# p2d-001.net
KiCad netlist of a schematic drawn in EAGLE
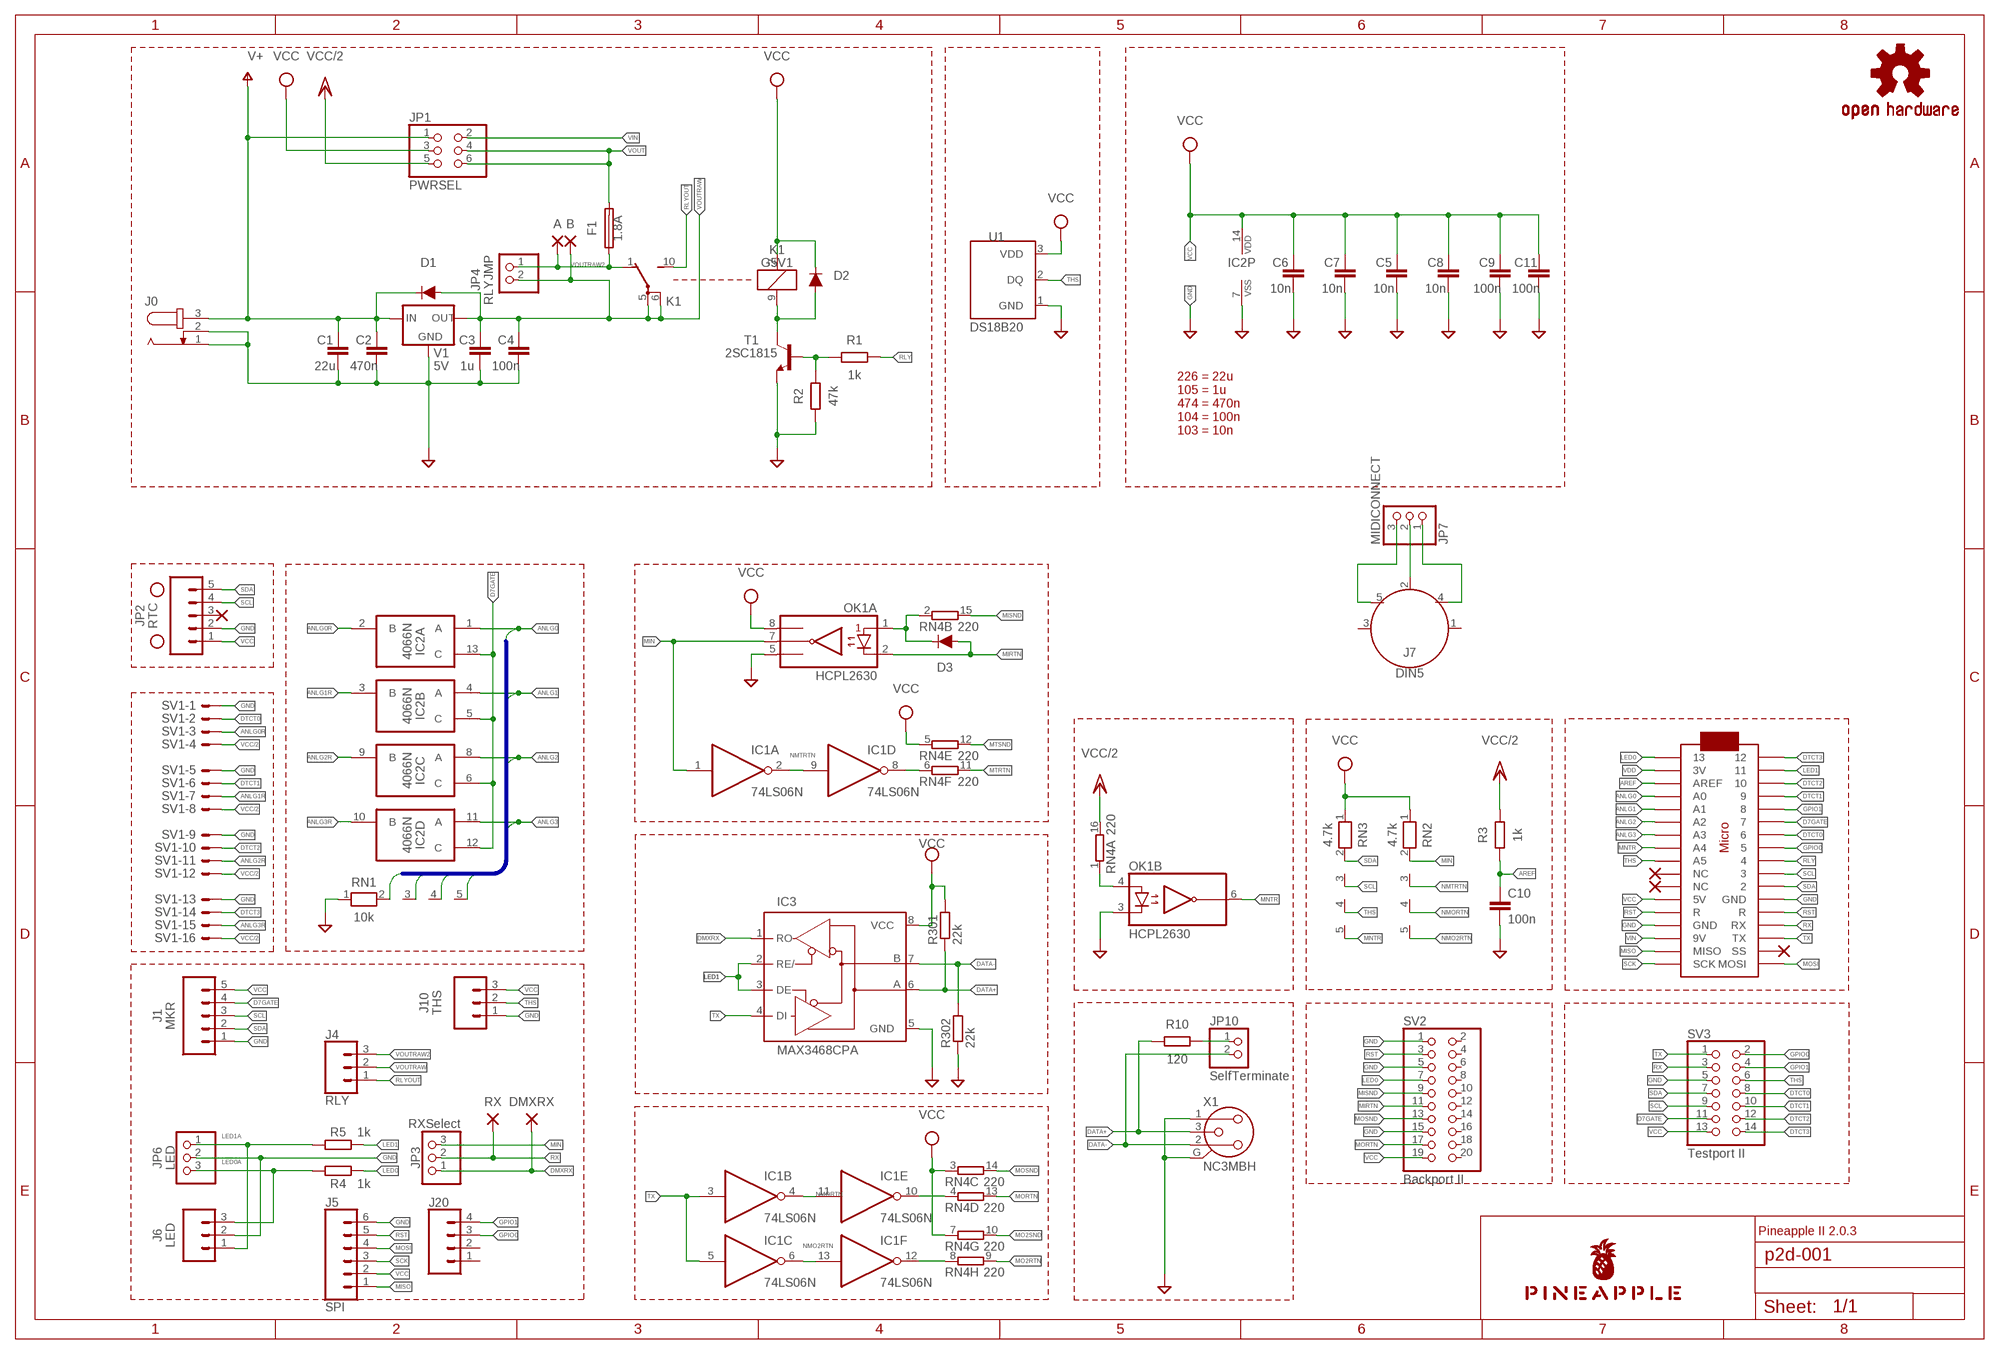
[diagram p0: schematic, sheet 1]

(export (version "E")
  (design (tool "Eeschema 10.0.6"))
  (components
    (comp (ref "A")
      (value "SMD2")
      (footprint "eagle-import:SMD1,27-2,54")
      (libsource (lib "eagle-import") (part "SMD2"))
    )
    (comp (ref "B")
      (value "SMD2")
      (footprint "eagle-import:SMD1,27-2,54")
      (libsource (lib "eagle-import") (part "SMD2"))
    )
    (comp (ref "C1")
      (value "22u")
      (footprint "eagle-import:C025-050X050")
      (libsource (lib "eagle-import") (part "C-EU025-050X050"))
    )
    (comp (ref "C2")
      (value "470n")
      (footprint "eagle-import:C050-024X044")
      (libsource (lib "eagle-import") (part "C-EU050-024X044"))
    )
    (comp (ref "C3")
      (value "1u")
      (footprint "eagle-import:C050-024X044")
      (libsource (lib "eagle-import") (part "C-EU050-024X044"))
    )
    (comp (ref "C4")
      (value "100n")
      (footprint "eagle-import:C025-024X044")
      (libsource (lib "eagle-import") (part "C-EU025-024X044"))
    )
    (comp (ref "C5")
      (value "10n")
      (footprint "eagle-import:C025-024X044")
      (libsource (lib "eagle-import") (part "resistor_348_C-EU025-024X044"))
    )
    (comp (ref "C6")
      (value "10n")
      (footprint "eagle-import:C025-024X044")
      (libsource (lib "eagle-import") (part "resistor_348_C-EU025-024X044"))
    )
    (comp (ref "C7")
      (value "10n")
      (footprint "eagle-import:C025-024X044")
      (libsource (lib "eagle-import") (part "resistor_348_C-EU025-024X044"))
    )
    (comp (ref "C8")
      (value "10n")
      (footprint "eagle-import:C025-024X044")
      (libsource (lib "eagle-import") (part "resistor_348_C-EU025-024X044"))
    )
    (comp (ref "C9")
      (value "100n")
      (footprint "eagle-import:C025-024X044")
      (libsource (lib "eagle-import") (part "resistor_348_C-EU025-024X044"))
    )
    (comp (ref "C10")
      (value "100n")
      (footprint "eagle-import:C025-024X044")
      (libsource (lib "eagle-import") (part "C-EU025-024X044"))
    )
    (comp (ref "C11")
      (value "100n")
      (footprint "eagle-import:C025-024X044")
      (libsource (lib "eagle-import") (part "resistor_348_C-EU025-024X044"))
    )
    (comp (ref "D1")
      (value "DIODE-1N4148")
      (footprint "eagle-import:DIODE-1N4148")
      (libsource (lib "eagle-import") (part "DIODE-1N4148"))
    )
    (comp (ref "D2")
      (value "DIODE-1N4148")
      (footprint "eagle-import:DIODE-1N4148")
      (libsource (lib "eagle-import") (part "DIODE-1N4148"))
    )
    (comp (ref "D3")
      (value "DIODE-1N4148")
      (footprint "eagle-import:DIODE-1N4148")
      (libsource (lib "eagle-import") (part "DIODE-1N4148"))
    )
    (comp (ref "DMXRX")
      (value "SMD2")
      (footprint "eagle-import:SMD1,27-2,54")
      (libsource (lib "eagle-import") (part "SMD2"))
    )
    (comp (ref "F1")
      (value "1.8A")
      (footprint "eagle-import:TE5")
      (libsource (lib "eagle-import") (part "TE5"))
    )
    (comp (ref "H1")
      (value "STAND-OFF")
      (footprint "eagle-import:STAND-OFF")
      (libsource (lib "eagle-import") (part "STAND-OFF"))
    )
    (comp (ref "H2")
      (value "STAND-OFF")
      (footprint "eagle-import:STAND-OFF")
      (libsource (lib "eagle-import") (part "STAND-OFF"))
    )
    (comp (ref "IC1")
      (value "74LS06N")
      (footprint "eagle-import:DIL14")
      (libsource (lib "eagle-import") (part "7406NLS"))
    )
    (comp (ref "IC2")
      (value "4066N")
      (footprint "eagle-import:DIL14")
      (libsource (lib "eagle-import") (part "4066N"))
    )
    (comp (ref "IC3")
      (value "MAX3468CPA")
      (footprint "eagle-import:DIL08")
      (libsource (lib "eagle-import") (part "MAX34PA68C"))
    )
    (comp (ref "J0")
      (value "JACK-PLUG0")
      (footprint "eagle-import:SPC4077")
      (libsource (lib "eagle-import") (part "JACK-PLUG0"))
    )
    (comp (ref "J1")
      (value "MKR")
      (footprint "eagle-import:JST-5-PTH")
      (libsource (lib "eagle-import") (part "CONN_05JST"))
    )
    (comp (ref "J4")
      (value "RLY")
      (footprint "eagle-import:JST-3-PTH-NS")
      (libsource (lib "eagle-import") (part "CONN_03JST-PTH-NS"))
    )
    (comp (ref "J5")
      (value "SPI")
      (footprint "eagle-import:1X06_1.27MM")
      (libsource (lib "eagle-import") (part "CONN_061.27MM"))
    )
    (comp (ref "J6")
      (value "LED")
      (footprint "eagle-import:JST-3-PTH-VERT")
      (libsource (lib "eagle-import") (part "CONN_03JST-PTH-VERT"))
    )
    (comp (ref "J7")
      (value "DIN5")
      (footprint "eagle-import:DIN5-RA-PTH")
      (libsource (lib "eagle-import") (part "DIN5"))
    )
    (comp (ref "J10")
      (value "THS")
      (footprint "eagle-import:JST-3-PTH")
      (libsource (lib "eagle-import") (part "CONN_03JST-PTH"))
    )
    (comp (ref "J20")
      (value "CONN_041.27MM")
      (footprint "eagle-import:1X04_1.27MM")
      (libsource (lib "eagle-import") (part "CONN_041.27MM"))
    )
    (comp (ref "JP1")
      (value "PWRSEL")
      (footprint "eagle-import:2X03")
      (libsource (lib "eagle-import") (part "PINHD-2X3"))
    )
    (comp (ref "JP2")
      (value "RTC")
      (footprint "eagle-import:1X05")
      (libsource (lib "eagle-import") (part "CONN_05"))
    )
    (comp (ref "JP3")
      (value "RXSelect")
      (footprint "eagle-import:1X03")
      (libsource (lib "eagle-import") (part "PINHD-1X3"))
    )
    (comp (ref "JP4")
      (value "RLYJMP")
      (footprint "eagle-import:1X02")
      (libsource (lib "eagle-import") (part "PINHD-1X2"))
    )
    (comp (ref "JP6")
      (value "LED")
      (footprint "eagle-import:1X03")
      (libsource (lib "eagle-import") (part "PINHD-1X3"))
    )
    (comp (ref "JP7")
      (value "MIDICONNECT")
      (footprint "eagle-import:1X03")
      (libsource (lib "eagle-import") (part "PINHD-1X3"))
    )
    (comp (ref "JP10")
      (value "SelfTerminate")
      (footprint "eagle-import:1X02")
      (libsource (lib "eagle-import") (part "PINHD-1X2"))
    )
    (comp (ref "K1")
      (value "G5V1")
      (footprint "eagle-import:G5V1")
      (fields (field (name "MPN") "G5V-1-DC24"))
      (libsource (lib "eagle-import") (part "G5V1"))
    )
    (comp (ref "LOGO1")
      (value "OSHW-LOGOS-COPPER")
      (footprint "eagle-import:OSHW-LOGO-S_COPPER")
      (libsource (lib "eagle-import") (part "OSHW-LOGOS-COPPER"))
    )
    (comp (ref "MC1")
      (value "ARDUINOMICRO")
      (footprint "eagle-import:ARDUINOMICRO")
      (libsource (lib "eagle-import") (part "ARDUINOMICRO"))
    )
    (comp (ref "OK1")
      (value "HCPL2630")
      (footprint "eagle-import:DIL08")
      (fields (field (name "MF") "AGILENT TECHNOLOGIES") (field (name "MPN") "HCPL-2630-000E"))
      (libsource (lib "eagle-import") (part "HCPL2630"))
    )
    (comp (ref "R1")
      (value "1k")
      (footprint "eagle-import:0204_5")
      (libsource (lib "eagle-import") (part "resistor_348_R-EU_0204/5"))
    )
    (comp (ref "R2")
      (value "47k")
      (footprint "eagle-import:0204_5")
      (libsource (lib "eagle-import") (part "resistor_348_R-EU_0204/5"))
    )
    (comp (ref "R3")
      (value "1k")
      (footprint "eagle-import:0204_5")
      (libsource (lib "eagle-import") (part "resistor_348_R-EU_0204/5"))
    )
    (comp (ref "R4")
      (value "1k")
      (footprint "eagle-import:0204_5")
      (libsource (lib "eagle-import") (part "resistor_348_R-EU_0204/5"))
    )
    (comp (ref "R5")
      (value "1k")
      (footprint "eagle-import:0204_5")
      (libsource (lib "eagle-import") (part "resistor_348_R-EU_0204/5"))
    )
    (comp (ref "R10")
      (value "120")
      (footprint "eagle-import:0204_5")
      (libsource (lib "eagle-import") (part "resistor_348_R-EU_0204/5"))
    )
    (comp (ref "R301")
      (value "22k")
      (footprint "eagle-import:M2012")
      (libsource (lib "eagle-import") (part "R-EU_M2012"))
    )
    (comp (ref "R302")
      (value "22k")
      (footprint "eagle-import:M2012")
      (libsource (lib "eagle-import") (part "R-EU_M2012"))
    )
    (comp (ref "RN1")
      (value "10k")
      (footprint "eagle-import:RN-5")
      (libsource (lib "eagle-import") (part "RN04"))
    )
    (comp (ref "RN2")
      (value "4.7k")
      (footprint "eagle-import:RN-5")
      (libsource (lib "eagle-import") (part "RN04"))
    )
    (comp (ref "RN3")
      (value "4.7k")
      (footprint "eagle-import:RN-5")
      (libsource (lib "eagle-import") (part "RN04"))
    )
    (comp (ref "RN4")
      (value "220")
      (footprint "eagle-import:DIL16")
      (libsource (lib "eagle-import") (part "8R-N"))
    )
    (comp (ref "RX")
      (value "SMD2")
      (footprint "eagle-import:SMD1,27-2,54")
      (libsource (lib "eagle-import") (part "SMD2"))
    )
    (comp (ref "SV1")
      (value "ML16LE")
      (footprint "eagle-import:ML16L")
      (libsource (lib "eagle-import") (part "ML16LE"))
    )
    (comp (ref "SV2")
      (value "Backport II")
      (footprint "eagle-import:2X10")
      (libsource (lib "eagle-import") (part "PINHD-2X10"))
    )
    (comp (ref "SV3")
      (value "Testport II")
      (footprint "eagle-import:2X07")
      (libsource (lib "eagle-import") (part "PINHD-2X7"))
    )
    (comp (ref "T1")
      (value "2SC1815")
      (footprint "eagle-import:TO92-ECB")
      (libsource (lib "eagle-import") (part "2SC1815"))
    )
    (comp (ref "U$1")
      (value "PINEAPPLE450_SILK")
      (footprint "eagle-import:PINEAPPLE450_SILK")
      (libsource (lib "eagle-import") (part "PINEAPPLE450_SILK"))
    )
    (comp (ref "U1")
      (value "DS18B20")
      (footprint "eagle-import:TO-92-AMMO")
      (libsource (lib "eagle-import") (part "DS18B20"))
    )
    (comp (ref "V1")
      (value "5V")
      (footprint "eagle-import:78XXL")
      (libsource (lib "eagle-import") (part "78XXL"))
    )
    (comp (ref "X1")
      (value "NC3MBH")
      (footprint "eagle-import:NC3MBH")
      (fields (field (name "MF") "NEUTRIK"))
      (libsource (lib "eagle-import") (part "NC3MBH"))
    )
  )
  (nets
    (net (code "1") (name "/LED0A") (class "Default")
      (node (ref "J6") (pin "3") (pinfunction "3_3") (pintype "passive"))
      (node (ref "JP6") (pin "3") (pinfunction "3_3") (pintype "passive"))
      (node (ref "R4") (pin "1") (pinfunction "1_1") (pintype "passive"))
    )
    (net (code "2") (name "/LED1A") (class "Default")
      (node (ref "J6") (pin "1") (pinfunction "1_1") (pintype "passive"))
      (node (ref "JP6") (pin "1") (pinfunction "1_1") (pintype "passive"))
      (node (ref "R5") (pin "1") (pinfunction "1_1") (pintype "passive"))
    )
    (net (code "3") (name "ANLG0") (class "Default")
      (node (ref "IC2") (pin "1") (pinfunction "A_1") (pintype "tri_state"))
      (node (ref "MC1") (pin "P$31") (pinfunction "A0_P$31") (pintype "bidirectional"))
      (node (ref "RN1") (pin "2") (pinfunction "2_2") (pintype "passive"))
    )
    (net (code "4") (name "ANLG0R") (class "Default")
      (node (ref "IC2") (pin "2") (pinfunction "B_2") (pintype "tri_state"))
      (node (ref "SV1") (pin "3") (pinfunction "S_3") (pintype "passive"))
    )
    (net (code "5") (name "ANLG1") (class "Default")
      (node (ref "IC2") (pin "4") (pinfunction "A_4") (pintype "tri_state"))
      (node (ref "MC1") (pin "P$30") (pinfunction "A1_P$30") (pintype "bidirectional"))
      (node (ref "RN1") (pin "3") (pinfunction "3_3") (pintype "passive"))
    )
    (net (code "6") (name "ANLG1R") (class "Default")
      (node (ref "IC2") (pin "3") (pinfunction "B_3") (pintype "tri_state"))
      (node (ref "SV1") (pin "7") (pinfunction "S_7") (pintype "passive"))
    )
    (net (code "7") (name "ANLG2") (class "Default")
      (node (ref "IC2") (pin "8") (pinfunction "A_8") (pintype "tri_state"))
      (node (ref "MC1") (pin "P$29") (pinfunction "A2_P$29") (pintype "bidirectional"))
      (node (ref "RN1") (pin "4") (pinfunction "4_4") (pintype "passive"))
    )
    (net (code "8") (name "ANLG2R") (class "Default")
      (node (ref "IC2") (pin "9") (pinfunction "B_9") (pintype "tri_state"))
      (node (ref "SV1") (pin "11") (pinfunction "S_11") (pintype "passive"))
    )
    (net (code "9") (name "ANLG3") (class "Default")
      (node (ref "IC2") (pin "11") (pinfunction "A_11") (pintype "tri_state"))
      (node (ref "MC1") (pin "P$28") (pinfunction "A3_P$28") (pintype "bidirectional"))
      (node (ref "RN1") (pin "5") (pinfunction "5_5") (pintype "passive"))
    )
    (net (code "10") (name "ANLG3R") (class "Default")
      (node (ref "IC2") (pin "10") (pinfunction "B_10") (pintype "tri_state"))
      (node (ref "SV1") (pin "15") (pinfunction "S_15") (pintype "passive"))
    )
    (net (code "11") (name "AREF") (class "Default")
      (node (ref "C10") (pin "1") (pinfunction "1_1") (pintype "passive"))
      (node (ref "MC1") (pin "P$32") (pinfunction "AREF_P$32") (pintype "bidirectional"))
      (node (ref "R3") (pin "1") (pinfunction "1_1") (pintype "passive"))
    )
    (net (code "12") (name "D7GATE") (class "Default")
      (node (ref "IC2") (pin "12") (pinfunction "C_12") (pintype "input"))
      (node (ref "IC2") (pin "13") (pinfunction "C_13") (pintype "input"))
      (node (ref "IC2") (pin "5") (pinfunction "C_5") (pintype "input"))
      (node (ref "IC2") (pin "6") (pinfunction "C_6") (pintype "input"))
      (node (ref "J1") (pin "4") (pinfunction "4_4") (pintype "passive"))
      (node (ref "MC1") (pin "P$6") (pinfunction "7_P$6") (pintype "bidirectional"))
      (node (ref "SV3") (pin "11") (pinfunction "11_11") (pintype "passive"))
    )
    (net (code "13") (name "DATA+") (class "Default")
      (node (ref "IC3") (pin "6") (pinfunction "A_6") (pintype "passive"))
      (node (ref "R10") (pin "1") (pinfunction "1_1") (pintype "passive"))
      (node (ref "R301") (pin "1") (pinfunction "1_1") (pintype "passive"))
      (node (ref "X1") (pin "3") (pinfunction "3_3") (pintype "passive"))
    )
    (net (code "14") (name "DATA-") (class "Default")
      (node (ref "IC3") (pin "7") (pinfunction "B_7") (pintype "passive"))
      (node (ref "JP10") (pin "2") (pinfunction "2_2") (pintype "passive"))
      (node (ref "R302") (pin "2") (pinfunction "2_2") (pintype "passive"))
      (node (ref "X1") (pin "2") (pinfunction "2_2") (pintype "passive"))
    )
    (net (code "15") (name "DMXRX") (class "Default")
      (node (ref "DMXRX") (pin "1") (pinfunction "P_1") (pintype "passive"))
      (node (ref "IC3") (pin "1") (pinfunction "RO_1") (pintype "output"))
      (node (ref "JP3") (pin "1") (pinfunction "1_1") (pintype "passive"))
    )
    (net (code "16") (name "DTCT0") (class "Default")
      (node (ref "MC1") (pin "P$7") (pinfunction "6_P$7") (pintype "bidirectional"))
      (node (ref "SV1") (pin "2") (pinfunction "S_2") (pintype "passive"))
      (node (ref "SV3") (pin "8") (pinfunction "8_8") (pintype "passive"))
    )
    (net (code "17") (name "DTCT1") (class "Default")
      (node (ref "MC1") (pin "P$4") (pinfunction "9_P$4") (pintype "bidirectional"))
      (node (ref "SV1") (pin "6") (pinfunction "S_6") (pintype "passive"))
      (node (ref "SV3") (pin "10") (pinfunction "10_10") (pintype "passive"))
    )
    (net (code "18") (name "DTCT2") (class "Default")
      (node (ref "MC1") (pin "P$3") (pinfunction "10_P$3") (pintype "bidirectional"))
      (node (ref "SV1") (pin "10") (pinfunction "S_10") (pintype "passive"))
      (node (ref "SV3") (pin "12") (pinfunction "12_12") (pintype "passive"))
    )
    (net (code "19") (name "DTCT3") (class "Default")
      (node (ref "MC1") (pin "P$1") (pinfunction "12_P$1") (pintype "bidirectional"))
      (node (ref "SV1") (pin "14") (pinfunction "S_14") (pintype "passive"))
      (node (ref "SV3") (pin "14") (pinfunction "14_14") (pintype "passive"))
    )
    (net (code "20") (name "GND") (class "Default")
      (node (ref "C1") (pin "2") (pinfunction "2_2") (pintype "passive"))
      (node (ref "C10") (pin "2") (pinfunction "2_2") (pintype "passive"))
      (node (ref "C11") (pin "2") (pinfunction "2_2") (pintype "passive"))
      (node (ref "C2") (pin "2") (pinfunction "2_2") (pintype "passive"))
      (node (ref "C3") (pin "2") (pinfunction "2_2") (pintype "passive"))
      (node (ref "C4") (pin "2") (pinfunction "2_2") (pintype "passive"))
      (node (ref "C5") (pin "2") (pinfunction "2_2") (pintype "passive"))
      (node (ref "C6") (pin "2") (pinfunction "2_2") (pintype "passive"))
      (node (ref "C7") (pin "2") (pinfunction "2_2") (pintype "passive"))
      (node (ref "C8") (pin "2") (pinfunction "2_2") (pintype "passive"))
      (node (ref "C9") (pin "2") (pinfunction "2_2") (pintype "passive"))
      (node (ref "IC2") (pin "7") (pinfunction "VSS_7") (pintype "power_in"))
      (node (ref "IC3") (pin "5") (pinfunction "GND_5") (pintype "power_in"))
      (node (ref "J0") (pin "1") (pinfunction "1_1") (pintype "passive"))
      (node (ref "J0") (pin "2") (pinfunction "2_2") (pintype "passive"))
      (node (ref "J1") (pin "1") (pinfunction "1_1") (pintype "passive"))
      (node (ref "J10") (pin "1") (pinfunction "1_1") (pintype "passive"))
      (node (ref "J5") (pin "6") (pinfunction "6_6") (pintype "passive"))
      (node (ref "J6") (pin "2") (pinfunction "2_2") (pintype "passive"))
      (node (ref "JP2") (pin "2") (pinfunction "2_2") (pintype "passive"))
      (node (ref "JP6") (pin "2") (pinfunction "2_2") (pintype "passive"))
      (node (ref "MC1") (pin "P$12") (pinfunction "GND_P$12") (pintype "bidirectional"))
      (node (ref "MC1") (pin "P$21") (pinfunction "GND_P$21") (pintype "bidirectional"))
      (node (ref "OK1") (pin "3") (pinfunction "C2_3") (pintype "passive"))
      (node (ref "OK1") (pin "5") (pinfunction "GND_5") (pintype "passive"))
      (node (ref "R2") (pin "1") (pinfunction "1_1") (pintype "passive"))
      (node (ref "R302") (pin "1") (pinfunction "1_1") (pintype "passive"))
      (node (ref "RN1") (pin "1") (pinfunction "1_1") (pintype "passive"))
      (node (ref "SV1") (pin "1") (pinfunction "S_1") (pintype "passive"))
      (node (ref "SV1") (pin "13") (pinfunction "S_13") (pintype "passive"))
      (node (ref "SV1") (pin "5") (pinfunction "S_5") (pintype "passive"))
      (node (ref "SV1") (pin "9") (pinfunction "S_9") (pintype "passive"))
      (node (ref "SV2") (pin "1") (pinfunction "1_1") (pintype "passive"))
      (node (ref "SV2") (pin "15") (pinfunction "15_15") (pintype "passive"))
      (node (ref "SV2") (pin "5") (pinfunction "5_5") (pintype "passive"))
      (node (ref "SV3") (pin "5") (pinfunction "5_5") (pintype "passive"))
      (node (ref "T1") (pin "E") (pinfunction "E_E") (pintype "passive"))
      (node (ref "U1") (pin "1") (pinfunction "GND_1") (pintype "power_in"))
      (node (ref "V1") (pin "GND") (pinfunction "GND_GND") (pintype "input"))
      (node (ref "X1") (pin "1") (pinfunction "1_1") (pintype "passive"))
      (node (ref "X1") (pin "G") (pinfunction "G_G") (pintype "passive"))
    )
    (net (code "21") (name "GPIO0") (class "Default")
      (node (ref "J20") (pin "3") (pinfunction "3_3") (pintype "passive"))
      (node (ref "MC1") (pin "P$8") (pinfunction "5_P$8") (pintype "bidirectional"))
      (node (ref "SV3") (pin "2") (pinfunction "2_2") (pintype "passive"))
    )
    (net (code "22") (name "GPIO1") (class "Default")
      (node (ref "J20") (pin "4") (pinfunction "4_4") (pintype "passive"))
      (node (ref "MC1") (pin "P$5") (pinfunction "8_P$5") (pintype "bidirectional"))
      (node (ref "SV3") (pin "4") (pinfunction "4_4") (pintype "passive"))
    )
    (net (code "23") (name "LED0") (class "Default")
      (node (ref "MC1") (pin "P$34") (pinfunction "13_P$34") (pintype "bidirectional"))
      (node (ref "R4") (pin "2") (pinfunction "2_2") (pintype "passive"))
      (node (ref "SV2") (pin "7") (pinfunction "7_7") (pintype "passive"))
    )
    (net (code "24") (name "LED1") (class "Default")
      (node (ref "IC3") (pin "2") (pinfunction "RE/_2") (pintype "input"))
      (node (ref "IC3") (pin "3") (pinfunction "DE_3") (pintype "input"))
      (node (ref "MC1") (pin "P$2") (pinfunction "11_P$2") (pintype "bidirectional"))
      (node (ref "R5") (pin "2") (pinfunction "2_2") (pintype "passive"))
    )
    (net (code "25") (name "MIN") (class "Default")
      (node (ref "IC1") (pin "1") (pinfunction "I_1") (pintype "input"))
      (node (ref "JP3") (pin "3") (pinfunction "3_3") (pintype "passive"))
      (node (ref "OK1") (pin "7") (pinfunction "VO1_7") (pintype "passive"))
      (node (ref "RN2") (pin "2") (pinfunction "2_2") (pintype "passive"))
    )
    (net (code "26") (name "MIRTN") (class "Default")
      (node (ref "D3") (pin "A") (pinfunction "A_A") (pintype "passive"))
      (node (ref "OK1") (pin "2") (pinfunction "C1_2") (pintype "passive"))
      (node (ref "SV2") (pin "11") (pinfunction "11_11") (pintype "passive"))
    )
    (net (code "27") (name "MISND") (class "Default")
      (node (ref "RN4") (pin "15") (pinfunction "2_15") (pintype "passive"))
      (node (ref "SV2") (pin "9") (pinfunction "9_9") (pintype "passive"))
    )
    (net (code "28") (name "MISO") (class "Default")
      (node (ref "J5") (pin "1") (pinfunction "1_1") (pintype "passive"))
      (node (ref "MC1") (pin "P$19") (pinfunction "MISO_P$19") (pintype "bidirectional"))
    )
    (net (code "29") (name "MNTR") (class "Default")
      (node (ref "MC1") (pin "P$27") (pinfunction "A4_P$27") (pintype "bidirectional"))
      (node (ref "OK1") (pin "6") (pinfunction "VO2_6") (pintype "passive"))
      (node (ref "RN3") (pin "5") (pinfunction "5_5") (pintype "passive"))
    )
    (net (code "30") (name "MO2RTN") (class "Default")
      (node (ref "RN4") (pin "9") (pinfunction "2_9") (pintype "passive"))
    )
    (net (code "31") (name "MO2SND") (class "Default")
      (node (ref "RN4") (pin "10") (pinfunction "2_10") (pintype "passive"))
    )
    (net (code "32") (name "MORTN") (class "Default")
      (node (ref "RN4") (pin "13") (pinfunction "2_13") (pintype "passive"))
      (node (ref "SV2") (pin "17") (pinfunction "17_17") (pintype "passive"))
    )
    (net (code "33") (name "MOSI") (class "Default")
      (node (ref "J5") (pin "4") (pinfunction "4_4") (pintype "passive"))
      (node (ref "MC1") (pin "P$17") (pinfunction "MOSI_P$17") (pintype "bidirectional"))
    )
    (net (code "34") (name "MOSND") (class "Default")
      (node (ref "RN4") (pin "14") (pinfunction "2_14") (pintype "passive"))
      (node (ref "SV2") (pin "13") (pinfunction "13_13") (pintype "passive"))
    )
    (net (code "35") (name "MTRTN") (class "Default")
      (node (ref "RN4") (pin "11") (pinfunction "2_11") (pintype "passive"))
    )
    (net (code "36") (name "MTSND") (class "Default")
      (node (ref "RN4") (pin "12") (pinfunction "2_12") (pintype "passive"))
    )
    (net (code "37") (name "NMO2RTN") (class "Default")
      (node (ref "IC1") (pin "13") (pinfunction "I_13") (pintype "input"))
      (node (ref "IC1") (pin "6") (pinfunction "O_6") (pintype "open_collector"))
      (node (ref "RN2") (pin "5") (pinfunction "5_5") (pintype "passive"))
    )
    (net (code "38") (name "NMORTN") (class "Default")
      (node (ref "IC1") (pin "11") (pinfunction "I_11") (pintype "input"))
      (node (ref "IC1") (pin "4") (pinfunction "O_4") (pintype "open_collector"))
      (node (ref "RN2") (pin "4") (pinfunction "4_4") (pintype "passive"))
    )
    (net (code "39") (name "NMTRTN") (class "Default")
      (node (ref "IC1") (pin "2") (pinfunction "O_2") (pintype "open_collector"))
      (node (ref "IC1") (pin "9") (pinfunction "I_9") (pintype "input"))
      (node (ref "RN2") (pin "3") (pinfunction "3_3") (pintype "passive"))
    )
    (net (code "40") (name "Net-(IC1D-O)") (class "Default")
      (node (ref "IC1") (pin "8") (pinfunction "O_8") (pintype "open_collector"))
      (node (ref "RN4") (pin "6") (pinfunction "1_6") (pintype "passive"))
    )
    (net (code "41") (name "Net-(IC1E-O)") (class "Default")
      (node (ref "IC1") (pin "10") (pinfunction "O_10") (pintype "open_collector"))
      (node (ref "RN4") (pin "4") (pinfunction "1_4") (pintype "passive"))
    )
    (net (code "42") (name "Net-(IC1F-O)") (class "Default")
      (node (ref "IC1") (pin "12") (pinfunction "O_12") (pintype "open_collector"))
      (node (ref "RN4") (pin "8") (pinfunction "1_8") (pintype "passive"))
    )
    (net (code "43") (name "Net-(J7-Pad2)") (class "Default")
      (node (ref "J7") (pin "2") (pinfunction "2_2") (pintype "bidirectional"))
      (node (ref "JP7") (pin "2") (pinfunction "2_2") (pintype "passive"))
    )
    (net (code "44") (name "Net-(J7-Pad4)") (class "Default")
      (node (ref "J7") (pin "4") (pinfunction "4_4") (pintype "bidirectional"))
      (node (ref "JP7") (pin "1") (pinfunction "1_1") (pintype "passive"))
    )
    (net (code "45") (name "Net-(J7-Pad5)") (class "Default")
      (node (ref "J7") (pin "5") (pinfunction "5_5") (pintype "bidirectional"))
      (node (ref "JP7") (pin "3") (pinfunction "3_3") (pintype "passive"))
    )
    (net (code "46") (name "Net-(JP10-Pad1)") (class "Default")
      (node (ref "JP10") (pin "1") (pinfunction "1_1") (pintype "passive"))
      (node (ref "R10") (pin "2") (pinfunction "2_2") (pintype "passive"))
    )
    (net (code "47") (name "Net-(K1A-2)") (class "Default")
      (node (ref "D2") (pin "A") (pinfunction "A_A") (pintype "passive"))
      (node (ref "K1") (pin "9") (pinfunction "2_9") (pintype "passive"))
      (node (ref "T1") (pin "C") (pinfunction "C_C") (pintype "passive"))
    )
    (net (code "48") (name "Net-(OK1A-A1)") (class "Default")
      (node (ref "D3") (pin "C") (pinfunction "C_C") (pintype "passive"))
      (node (ref "OK1") (pin "1") (pinfunction "A1_1") (pintype "passive"))
      (node (ref "RN4") (pin "2") (pinfunction "1_2") (pintype "passive"))
    )
    (net (code "49") (name "Net-(OK1B-A2)") (class "Default")
      (node (ref "OK1") (pin "4") (pinfunction "A2_4") (pintype "passive"))
      (node (ref "RN4") (pin "1") (pinfunction "1_1") (pintype "passive"))
    )
    (net (code "50") (name "Net-(R1-Pad1)") (class "Default")
      (node (ref "R1") (pin "1") (pinfunction "1_1") (pintype "passive"))
      (node (ref "R2") (pin "2") (pinfunction "2_2") (pintype "passive"))
      (node (ref "T1") (pin "B") (pinfunction "B_B") (pintype "passive"))
    )
    (net (code "51") (name "RLY") (class "Default")
      (node (ref "MC1") (pin "P$9") (pinfunction "4_P$9") (pintype "bidirectional"))
      (node (ref "R1") (pin "2") (pinfunction "2_2") (pintype "passive"))
    )
    (net (code "52") (name "RLYOUT") (class "Default")
      (node (ref "J4") (pin "1") (pinfunction "1_1") (pintype "passive"))
      (node (ref "K1") (pin "10") (pinfunction "S_10") (pintype "passive"))
    )
    (net (code "53") (name "RST") (class "Default")
      (node (ref "J5") (pin "5") (pinfunction "5_5") (pintype "passive"))
      (node (ref "MC1") (pin "P$13") (pinfunction "R_P$13") (pintype "bidirectional"))
      (node (ref "MC1") (pin "P$22") (pinfunction "R_P$22") (pintype "bidirectional"))
      (node (ref "SV2") (pin "3") (pinfunction "3_3") (pintype "passive"))
    )
    (net (code "54") (name "RX") (class "Default")
      (node (ref "JP3") (pin "2") (pinfunction "2_2") (pintype "passive"))
      (node (ref "MC1") (pin "P$14") (pinfunction "RX_P$14") (pintype "bidirectional"))
      (node (ref "RX") (pin "1") (pinfunction "P_1") (pintype "passive"))
      (node (ref "SV3") (pin "3") (pinfunction "3_3") (pintype "passive"))
    )
    (net (code "55") (name "SCK") (class "Default")
      (node (ref "J5") (pin "3") (pinfunction "3_3") (pintype "passive"))
      (node (ref "MC1") (pin "P$18") (pinfunction "SCK_P$18") (pintype "bidirectional"))
    )
    (net (code "56") (name "SCL") (class "Default")
      (node (ref "J1") (pin "3") (pinfunction "3_3") (pintype "passive"))
      (node (ref "JP2") (pin "4") (pinfunction "4_4") (pintype "passive"))
      (node (ref "MC1") (pin "P$10") (pinfunction "3_P$10") (pintype "bidirectional"))
      (node (ref "RN3") (pin "3") (pinfunction "3_3") (pintype "passive"))
      (node (ref "SV3") (pin "9") (pinfunction "9_9") (pintype "passive"))
    )
    (net (code "57") (name "SDA") (class "Default")
      (node (ref "J1") (pin "2") (pinfunction "2_2") (pintype "passive"))
      (node (ref "JP2") (pin "5") (pinfunction "5_5") (pintype "passive"))
      (node (ref "MC1") (pin "P$11") (pinfunction "2_P$11") (pintype "bidirectional"))
      (node (ref "RN3") (pin "2") (pinfunction "2_2") (pintype "passive"))
      (node (ref "SV3") (pin "7") (pinfunction "7_7") (pintype "passive"))
    )
    (net (code "58") (name "THS") (class "Default")
      (node (ref "J10") (pin "2") (pinfunction "2_2") (pintype "passive"))
      (node (ref "MC1") (pin "P$26") (pinfunction "A5_P$26") (pintype "bidirectional"))
      (node (ref "RN3") (pin "4") (pinfunction "4_4") (pintype "passive"))
      (node (ref "SV3") (pin "6") (pinfunction "6_6") (pintype "passive"))
      (node (ref "U1") (pin "2") (pinfunction "DQ_2") (pintype "bidirectional"))
    )
    (net (code "59") (name "TX") (class "Default")
      (node (ref "IC1") (pin "3") (pinfunction "I_3") (pintype "input"))
      (node (ref "IC1") (pin "5") (pinfunction "I_5") (pintype "input"))
      (node (ref "IC3") (pin "4") (pinfunction "DI_4") (pintype "input"))
      (node (ref "MC1") (pin "P$15") (pinfunction "TX_P$15") (pintype "bidirectional"))
      (node (ref "SV3") (pin "1") (pinfunction "1_1") (pintype "passive"))
    )
    (net (code "60") (name "V+") (class "Default")
      (node (ref "C1") (pin "1") (pinfunction "1_1") (pintype "passive"))
      (node (ref "C2") (pin "1") (pinfunction "1_1") (pintype "passive"))
      (node (ref "D1") (pin "C") (pinfunction "C_C") (pintype "passive"))
      (node (ref "J0") (pin "3") (pinfunction "3_3") (pintype "passive"))
      (node (ref "JP1") (pin "1") (pinfunction "1_1") (pintype "passive"))
      (node (ref "V1") (pin "IN") (pinfunction "IN_IN") (pintype "input"))
    )
    (net (code "61") (name "VCC") (class "Default")
      (node (ref "C11") (pin "1") (pinfunction "1_1") (pintype "passive"))
      (node (ref "C5") (pin "1") (pinfunction "1_1") (pintype "passive"))
      (node (ref "C6") (pin "1") (pinfunction "1_1") (pintype "passive"))
      (node (ref "C7") (pin "1") (pinfunction "1_1") (pintype "passive"))
      (node (ref "C8") (pin "1") (pinfunction "1_1") (pintype "passive"))
      (node (ref "C9") (pin "1") (pinfunction "1_1") (pintype "passive"))
      (node (ref "D2") (pin "C") (pinfunction "C_C") (pintype "passive"))
      (node (ref "IC2") (pin "14") (pinfunction "VDD_14") (pintype "power_in"))
      (node (ref "IC3") (pin "8") (pinfunction "VCC_8") (pintype "power_in"))
      (node (ref "J1") (pin "5") (pinfunction "5_5") (pintype "passive"))
      (node (ref "J10") (pin "3") (pinfunction "3_3") (pintype "passive"))
      (node (ref "J5") (pin "2") (pinfunction "2_2") (pintype "passive"))
      (node (ref "JP1") (pin "3") (pinfunction "3_3") (pintype "passive"))
      (node (ref "JP2") (pin "1") (pinfunction "1_1") (pintype "passive"))
      (node (ref "K1") (pin "2") (pinfunction "1_2") (pintype "passive"))
      (node (ref "MC1") (pin "P$23") (pinfunction "5V_P$23") (pintype "bidirectional"))
      (node (ref "OK1") (pin "8") (pinfunction "VCC_8") (pintype "passive"))
      (node (ref "R301") (pin "2") (pinfunction "2_2") (pintype "passive"))
      (node (ref "RN2") (pin "1") (pinfunction "1_1") (pintype "passive"))
      (node (ref "RN3") (pin "1") (pinfunction "1_1") (pintype "passive"))
      (node (ref "RN4") (pin "3") (pinfunction "1_3") (pintype "passive"))
      (node (ref "RN4") (pin "5") (pinfunction "1_5") (pintype "passive"))
      (node (ref "RN4") (pin "7") (pinfunction "1_7") (pintype "passive"))
      (node (ref "SV2") (pin "19") (pinfunction "19_19") (pintype "passive"))
      (node (ref "SV3") (pin "13") (pinfunction "13_13") (pintype "passive"))
      (node (ref "U1") (pin "3") (pinfunction "VDD_3") (pintype "power_in"))
    )
    (net (code "62") (name "VCC{slash}2") (class "Default")
      (node (ref "JP1") (pin "5") (pinfunction "5_5") (pintype "passive"))
      (node (ref "R3") (pin "2") (pinfunction "2_2") (pintype "passive"))
      (node (ref "RN4") (pin "16") (pinfunction "2_16") (pintype "passive"))
      (node (ref "SV1") (pin "12") (pinfunction "S_12") (pintype "passive"))
      (node (ref "SV1") (pin "16") (pinfunction "S_16") (pintype "passive"))
      (node (ref "SV1") (pin "4") (pinfunction "S_4") (pintype "passive"))
      (node (ref "SV1") (pin "8") (pinfunction "S_8") (pintype "passive"))
    )
    (net (code "63") (name "VDD") (class "Default")
      (node (ref "MC1") (pin "P$33") (pinfunction "3V_P$33") (pintype "bidirectional"))
    )
    (net (code "64") (name "VIN") (class "Default")
      (node (ref "JP1") (pin "2") (pinfunction "2_2") (pintype "passive"))
      (node (ref "MC1") (pin "P$20") (pinfunction "9V_P$20") (pintype "bidirectional"))
    )
    (net (code "65") (name "VOUT") (class "Default")
      (node (ref "F1") (pin "2") (pinfunction "2_2") (pintype "passive"))
      (node (ref "JP1") (pin "4") (pinfunction "4_4") (pintype "passive"))
      (node (ref "JP1") (pin "6") (pinfunction "6_6") (pintype "passive"))
    )
    (net (code "66") (name "VOUTRAW") (class "Default")
      (node (ref "B") (pin "1") (pinfunction "P_1") (pintype "passive"))
      (node (ref "C3") (pin "1") (pinfunction "1_1") (pintype "passive"))
      (node (ref "C4") (pin "1") (pinfunction "1_1") (pintype "passive"))
      (node (ref "D1") (pin "A") (pinfunction "A_A") (pintype "passive"))
      (node (ref "J4") (pin "2") (pinfunction "2_2") (pintype "passive"))
      (node (ref "JP4") (pin "2") (pinfunction "2_2") (pintype "passive"))
      (node (ref "K1") (pin "5") (pinfunction "P_5") (pintype "passive"))
      (node (ref "K1") (pin "6") (pinfunction "P_6") (pintype "passive"))
      (node (ref "V1") (pin "OUT") (pinfunction "OUT_OUT") (pintype "passive"))
    )
    (net (code "67") (name "VOUTRAW2") (class "Default")
      (node (ref "A") (pin "1") (pinfunction "P_1") (pintype "passive"))
      (node (ref "F1") (pin "1") (pinfunction "1_1") (pintype "passive"))
      (node (ref "J4") (pin "3") (pinfunction "3_3") (pintype "passive"))
      (node (ref "JP4") (pin "1") (pinfunction "1_1") (pintype "passive"))
      (node (ref "K1") (pin "1") (pinfunction "O_1") (pintype "passive"))
    )
    (net (code "68") (name "unconnected-(J7-Pad1)") (class "Default")
      (node (ref "J7") (pin "1") (pinfunction "1_1") (pintype "bidirectional"))
    )
    (net (code "69") (name "unconnected-(J7-Pad3)") (class "Default")
      (node (ref "J7") (pin "3") (pinfunction "3_3") (pintype "bidirectional"))
    )
    (net (code "70") (name "unconnected-(J20-Pad1)") (class "Default")
      (node (ref "J20") (pin "1") (pinfunction "1_1") (pintype "passive"))
    )
    (net (code "71") (name "unconnected-(J20-Pad2)") (class "Default")
      (node (ref "J20") (pin "2") (pinfunction "2_2") (pintype "passive"))
    )
    (net (code "72") (name "unconnected-(JP2-Pad3)") (class "Default")
      (node (ref "JP2") (pin "3") (pinfunction "3_3") (pintype "passive"))
    )
    (net (code "73") (name "unconnected-(MC1-NC-PadP$24)") (class "Default")
      (node (ref "MC1") (pin "P$24") (pinfunction "NC_P$24") (pintype "bidirectional"))
    )
    (net (code "74") (name "unconnected-(MC1-NC-PadP$25)") (class "Default")
      (node (ref "MC1") (pin "P$25") (pinfunction "NC_P$25") (pintype "bidirectional"))
    )
    (net (code "75") (name "unconnected-(MC1-SS-PadP$16)") (class "Default")
      (node (ref "MC1") (pin "P$16") (pinfunction "SS_P$16") (pintype "bidirectional"))
    )
    (net (code "76") (name "unconnected-(SV2-Pad2)") (class "Default")
      (node (ref "SV2") (pin "2") (pinfunction "2_2") (pintype "passive"))
    )
    (net (code "77") (name "unconnected-(SV2-Pad4)") (class "Default")
      (node (ref "SV2") (pin "4") (pinfunction "4_4") (pintype "passive"))
    )
    (net (code "78") (name "unconnected-(SV2-Pad6)") (class "Default")
      (node (ref "SV2") (pin "6") (pinfunction "6_6") (pintype "passive"))
    )
    (net (code "79") (name "unconnected-(SV2-Pad8)") (class "Default")
      (node (ref "SV2") (pin "8") (pinfunction "8_8") (pintype "passive"))
    )
    (net (code "80") (name "unconnected-(SV2-Pad10)") (class "Default")
      (node (ref "SV2") (pin "10") (pinfunction "10_10") (pintype "passive"))
    )
    (net (code "81") (name "unconnected-(SV2-Pad12)") (class "Default")
      (node (ref "SV2") (pin "12") (pinfunction "12_12") (pintype "passive"))
    )
    (net (code "82") (name "unconnected-(SV2-Pad14)") (class "Default")
      (node (ref "SV2") (pin "14") (pinfunction "14_14") (pintype "passive"))
    )
    (net (code "83") (name "unconnected-(SV2-Pad16)") (class "Default")
      (node (ref "SV2") (pin "16") (pinfunction "16_16") (pintype "passive"))
    )
    (net (code "84") (name "unconnected-(SV2-Pad18)") (class "Default")
      (node (ref "SV2") (pin "18") (pinfunction "18_18") (pintype "passive"))
    )
    (net (code "85") (name "unconnected-(SV2-Pad20)") (class "Default")
      (node (ref "SV2") (pin "20") (pinfunction "20_20") (pintype "passive"))
    )
  )
)
